# TC2030-MCP-NL-Adapter.net
KiCad netlist of a schematic drawn in EAGLE
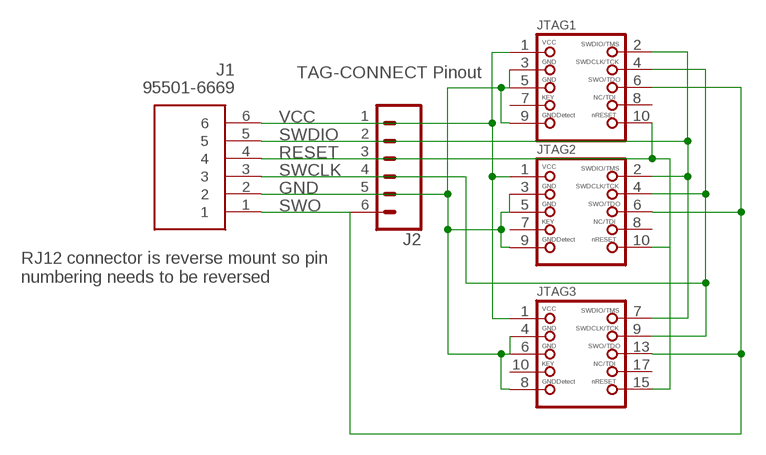
[diagram p0: schematic, sheet 1]

(export (version "E")
  (design (tool "Eeschema 10.0.6"))
  (components
    (comp (ref "J1")
      (value "95501-6669")
      (footprint "eagle-import:95501-6669")
      (fields (field (name "MOUSER_PART_NUMBER") "538-95501-6669"))
      (libsource (lib "eagle-import") (part "95501-6669"))
    )
    (comp (ref "J2")
      (value "CONN_06SILK_FEMALE_PTH")
      (footprint "eagle-import:1X06")
      (libsource (lib "eagle-import") (part "CONN_06SILK_FEMALE_PTH"))
    )
    (comp (ref "JTAG1")
      (value "JTAG-CORTEXM3")
      (footprint "eagle-import:2X05_1.27MM_SMT")
      (libsource (lib "eagle-import") (part "JTAG-CORTEXM3"))
    )
    (comp (ref "JTAG2")
      (value "JTAG-CORTEXM3MOLEX")
      (footprint "eagle-import:CORTEXM3_SWD10_MOLEX")
      (libsource (lib "eagle-import") (part "JTAG-CORTEXM3MOLEX"))
    )
    (comp (ref "JTAG3")
      (value "JTAG-CORTEXM3MOLEX20")
      (footprint "eagle-import:JTAG-ARM")
      (libsource (lib "eagle-import") (part "JTAG-CORTEXM3MOLEX20"))
    )
  )
  (nets
    (net (code "1") (name "/GND") (class "Default")
      (node (ref "J1") (pin "2") (pinfunction "2_2") (pintype "bidirectional"))
      (node (ref "J2") (pin "5") (pinfunction "5_5") (pintype "passive"))
      (node (ref "JTAG1") (pin "3") (pinfunction "3_3") (pintype "passive"))
      (node (ref "JTAG1") (pin "5") (pinfunction "5_5") (pintype "passive"))
      (node (ref "JTAG1") (pin "9") (pinfunction "9_9") (pintype "passive"))
      (node (ref "JTAG2") (pin "3") (pinfunction "3_3") (pintype "passive"))
      (node (ref "JTAG2") (pin "5") (pinfunction "5_5") (pintype "passive"))
      (node (ref "JTAG2") (pin "9") (pinfunction "9_9") (pintype "passive"))
      (node (ref "JTAG3") (pin "4") (pinfunction "3_4") (pintype "passive"))
      (node (ref "JTAG3") (pin "6") (pinfunction "5_6") (pintype "passive"))
      (node (ref "JTAG3") (pin "8") (pinfunction "9_8") (pintype "passive"))
    )
    (net (code "2") (name "/RESET") (class "Default")
      (node (ref "J1") (pin "4") (pinfunction "4_4") (pintype "bidirectional"))
      (node (ref "J2") (pin "3") (pinfunction "3_3") (pintype "passive"))
      (node (ref "JTAG1") (pin "10") (pinfunction "10_10") (pintype "passive"))
      (node (ref "JTAG2") (pin "10") (pinfunction "10_10") (pintype "passive"))
      (node (ref "JTAG3") (pin "15") (pinfunction "10_15") (pintype "passive"))
    )
    (net (code "3") (name "/SWCLK") (class "Default")
      (node (ref "J1") (pin "3") (pinfunction "3_3") (pintype "bidirectional"))
      (node (ref "J2") (pin "4") (pinfunction "4_4") (pintype "passive"))
      (node (ref "JTAG1") (pin "4") (pinfunction "4_4") (pintype "passive"))
      (node (ref "JTAG2") (pin "4") (pinfunction "4_4") (pintype "passive"))
      (node (ref "JTAG3") (pin "9") (pinfunction "4_9") (pintype "passive"))
    )
    (net (code "4") (name "/SWDIO") (class "Default")
      (node (ref "J1") (pin "5") (pinfunction "5_5") (pintype "bidirectional"))
      (node (ref "J2") (pin "2") (pinfunction "2_2") (pintype "passive"))
      (node (ref "JTAG1") (pin "2") (pinfunction "2_2") (pintype "passive"))
      (node (ref "JTAG2") (pin "2") (pinfunction "2_2") (pintype "passive"))
      (node (ref "JTAG3") (pin "7") (pinfunction "2_7") (pintype "passive"))
    )
    (net (code "5") (name "/SWO") (class "Default")
      (node (ref "J1") (pin "1") (pinfunction "1_1") (pintype "bidirectional"))
      (node (ref "J2") (pin "6") (pinfunction "6_6") (pintype "passive"))
      (node (ref "JTAG1") (pin "6") (pinfunction "6_6") (pintype "passive"))
      (node (ref "JTAG2") (pin "6") (pinfunction "6_6") (pintype "passive"))
      (node (ref "JTAG3") (pin "13") (pinfunction "6_13") (pintype "passive"))
    )
    (net (code "6") (name "/VCC") (class "Default")
      (node (ref "J1") (pin "6") (pinfunction "6_6") (pintype "bidirectional"))
      (node (ref "J2") (pin "1") (pinfunction "1_1") (pintype "passive"))
      (node (ref "JTAG1") (pin "1") (pinfunction "1_1") (pintype "passive"))
      (node (ref "JTAG2") (pin "1") (pinfunction "1_1") (pintype "passive"))
      (node (ref "JTAG3") (pin "1") (pinfunction "1_1") (pintype "passive"))
    )
    (net (code "7") (name "unconnected-(JTAG1-Pad7)") (class "Default")
      (node (ref "JTAG1") (pin "7") (pinfunction "7_7") (pintype "passive"))
    )
    (net (code "8") (name "unconnected-(JTAG1-Pad8)") (class "Default")
      (node (ref "JTAG1") (pin "8") (pinfunction "8_8") (pintype "passive"))
    )
    (net (code "9") (name "unconnected-(JTAG2-Pad7)") (class "Default")
      (node (ref "JTAG2") (pin "7") (pinfunction "7_7") (pintype "passive"))
    )
    (net (code "10") (name "unconnected-(JTAG2-Pad8)") (class "Default")
      (node (ref "JTAG2") (pin "8") (pinfunction "8_8") (pintype "passive"))
    )
    (net (code "11") (name "unconnected-(JTAG3-7-Pad10)") (class "Default")
      (node (ref "JTAG3") (pin "10") (pinfunction "7_10") (pintype "passive"))
    )
    (net (code "12") (name "unconnected-(JTAG3-8-Pad17)") (class "Default")
      (node (ref "JTAG3") (pin "17") (pinfunction "8_17") (pintype "passive"))
    )
  )
)
